# SCH_USB-Hub-Reader_2024-05-11.net
KiCad netlist of a schematic drawn in EasyEDA
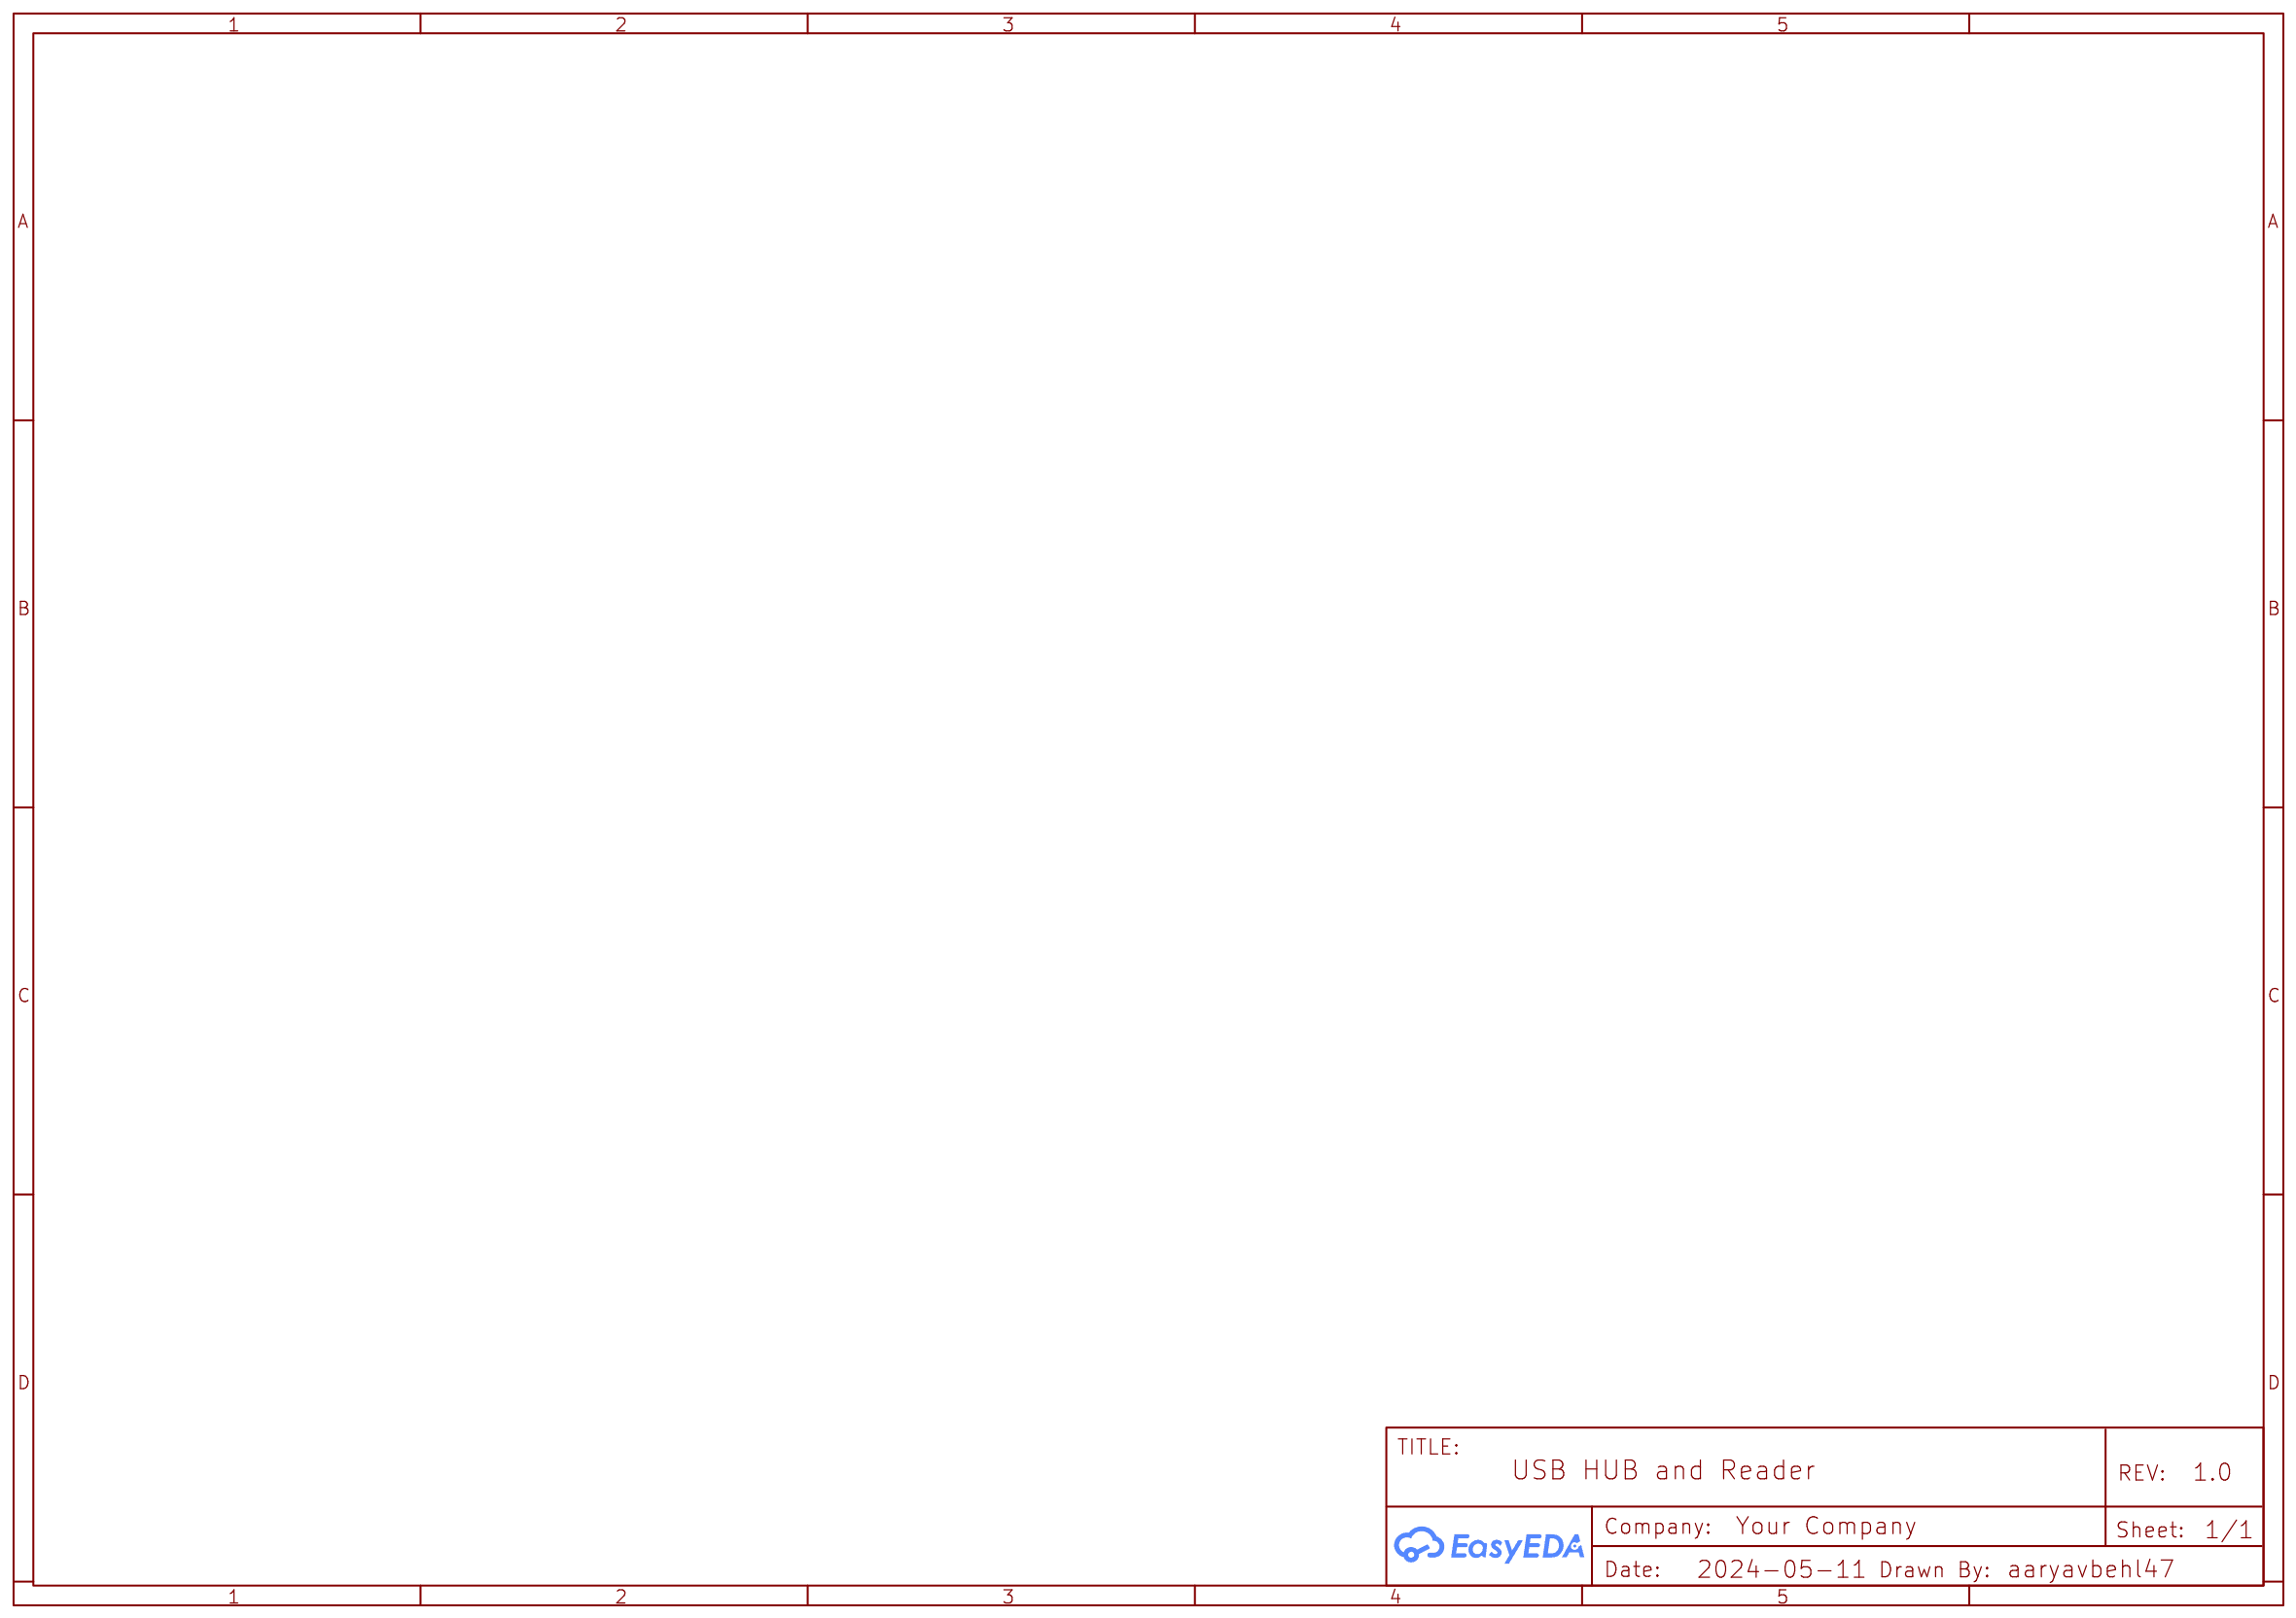
[diagram p0: Sheet_1]
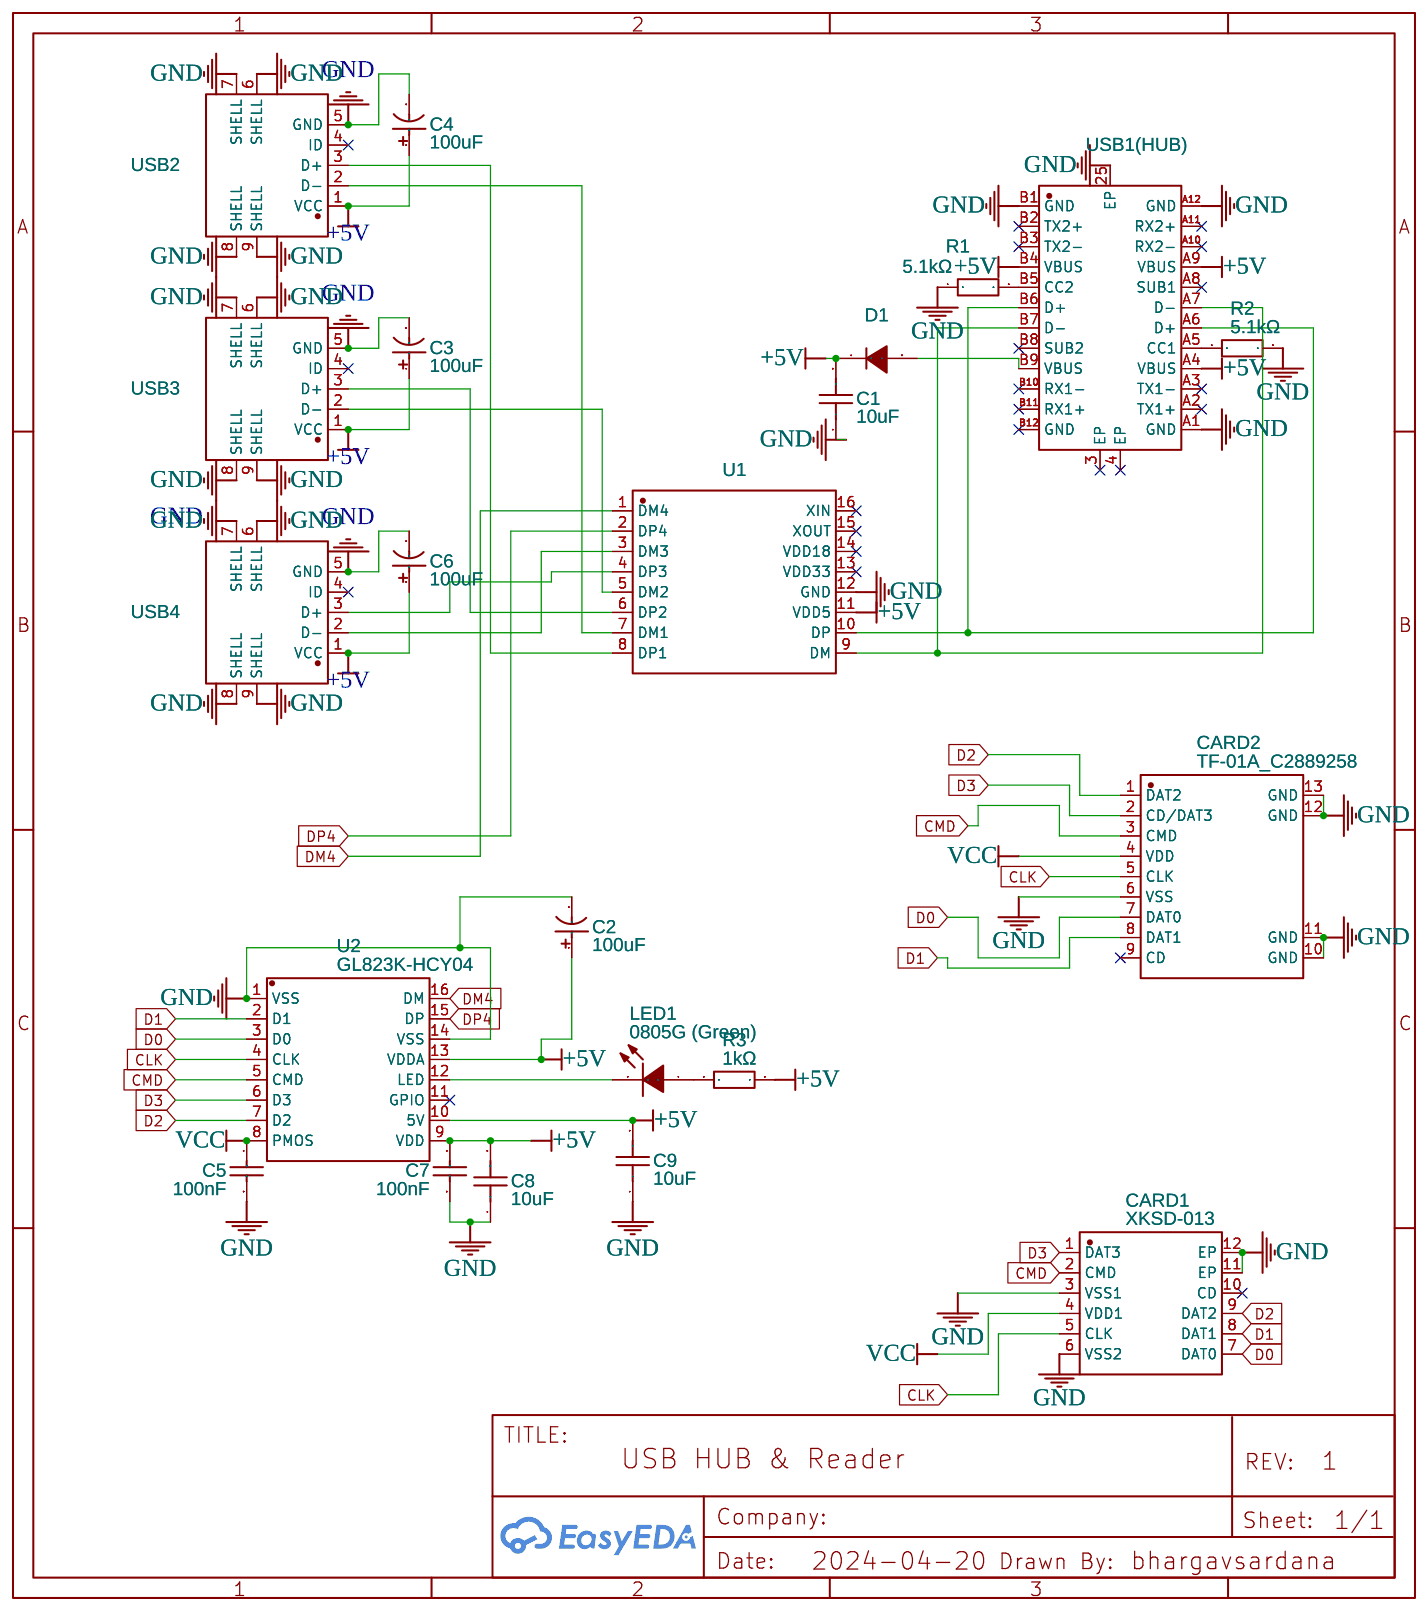
[diagram p1: hub schematics]

(export (version "E")
  (design (tool "Eeschema 10.0.6"))
  (components
    (comp (ref "C1")
      (value "10uF")
      (fields
        (field (name "Manufacturer Part") "CL10A106KP8NNNC")
        (field (name "Manufacturer") "SAMSUNG(三星)")
      )
      (libsource (lib "") (part "CL10A106KP8NNNC"))
    )
    (comp (ref "C2")
      (value "100uF")
      (fields (field (name "Manufacturer Part") "RVT1J101M1010") (field (name "Manufacturer") "ROQANG(容强)"))
      (libsource (lib "") (part "RVT1J101M1010-C72481"))
    )
    (comp (ref "C3")
      (value "100uF")
      (fields (field (name "Manufacturer Part") "RVT1J101M1010") (field (name "Manufacturer") "ROQANG(容强)"))
      (libsource (lib "") (part "RVT1J101M1010-C72481"))
    )
    (comp (ref "C4")
      (value "100uF")
      (fields (field (name "Manufacturer Part") "RVT1J101M1010") (field (name "Manufacturer") "ROQANG(容强)"))
      (libsource (lib "") (part "RVT1J101M1010-C72481"))
    )
    (comp (ref "C5")
      (value "100nF")
      (fields
        (field (name "Manufacturer Part") "CL05B104KO5NNNC")
        (field (name "Manufacturer") "SAMSUNG(三星)")
      )
      (libsource (lib "") (part "CL05B104KO5NNNC"))
    )
    (comp (ref "C6")
      (value "100uF")
      (fields (field (name "Manufacturer Part") "RVT1J101M1010") (field (name "Manufacturer") "ROQANG(容强)"))
      (libsource (lib "") (part "RVT1J101M1010-C72481"))
    )
    (comp (ref "C7")
      (value "100nF")
      (fields
        (field (name "Manufacturer Part") "CL05B104KO5NNNC")
        (field (name "Manufacturer") "SAMSUNG(三星)")
      )
      (libsource (lib "") (part "CL05B104KO5NNNC"))
    )
    (comp (ref "C8")
      (value "10uF")
      (fields
        (field (name "Manufacturer Part") "CL10A106KP8NNNC")
        (field (name "Manufacturer") "SAMSUNG(三星)")
      )
      (libsource (lib "") (part "CL10A106KP8NNNC"))
    )
    (comp (ref "C9")
      (value "10uF")
      (fields
        (field (name "Manufacturer Part") "CL10A106KP8NNNC")
        (field (name "Manufacturer") "SAMSUNG(三星)")
      )
      (libsource (lib "") (part "CL10A106KP8NNNC"))
    )
    (comp (ref "CARD1")
      (value "XKSD-013")
      (fields (field (name "Manufacturer") "XKB Connectivity(中国星坤)"))
      (libsource (lib "") (part "XKSD-013"))
    )
    (comp (ref "CARD2")
      (value "TF-01A_C2889258")
      (fields (field (name "Manufacturer Part") "TF-01A") (field (name "Manufacturer") "Yuandi(台湾元迪)"))
      (libsource (lib "") (part "TF-01A_C2889258"))
    )
    (comp (ref "D1")
      (value "NSR0320MW2T1G")
      (fields (field (name "Manufacturer") "onsemi(安森美)"))
      (libsource (lib "") (part "NSR0320MW2T1G"))
    )
    (comp (ref "LED1")
      (value "0805G (Green)")
      (fields (field (name "Manufacturer Part") "KT-0805G") (field (name "Manufacturer") "KENTO"))
      (libsource (lib "") (part "0805G (Green)"))
    )
    (comp (ref "R1")
      (value "5.1kΩ")
      (fields
        (field (name "Manufacturer Part") "0402WGF5101TCE")
        (field (name "Manufacturer") "UNI-ROYAL(厚声)")
      )
      (libsource (lib "") (part "0402WGF5101TCE"))
    )
    (comp (ref "R2")
      (value "5.1kΩ")
      (fields
        (field (name "Manufacturer Part") "0402WGF5101TCE")
        (field (name "Manufacturer") "UNI-ROYAL(厚声)")
      )
      (libsource (lib "") (part "0402WGF5101TCE"))
    )
    (comp (ref "R3")
      (value "1kΩ")
      (fields
        (field (name "Manufacturer Part") "0402WGF1001TCE")
        (field (name "Manufacturer") "UNI-ROYAL(厚声)")
      )
      (libsource (lib "") (part "0402WGF1001TCE"))
    )
    (comp (ref "U1")
      (value "SL2.1A")
      (fields (field (name "Manufacturer") "CoreChips(和芯润德)"))
      (libsource (lib "") (part "SL2.1A"))
    )
    (comp (ref "U2")
      (value "GL823K-HCY04")
      (fields (field (name "Manufacturer") "GENESYS(创惟)"))
      (libsource (lib "") (part "GL823K-HCY04"))
    )
    (comp (ref "USB1(HUB)")
      (value "TYPE-C 24P QT")
      (fields (field (name "Manufacturer") "SHOU HAN(首韩)"))
      (libsource (lib "") (part "TYPE-C 24P QT"))
    )
    (comp (ref "USB2")
      (value "U224-051N-3GRA035")
      (fields (field (name "Manufacturer") "XKB Connectivity(中国星坤)"))
      (libsource (lib "") (part "U224-051N-3GRA035"))
    )
    (comp (ref "USB3")
      (value "U224-051N-3GRA035")
      (fields (field (name "Manufacturer") "XKB Connectivity(中国星坤)"))
      (libsource (lib "") (part "U224-051N-3GRA035"))
    )
    (comp (ref "USB4")
      (value "U224-051N-3GRA035")
      (fields (field (name "Manufacturer") "XKB Connectivity(中国星坤)"))
      (libsource (lib "") (part "U224-051N-3GRA035"))
    )
  )
  (nets
    (net (code "1") (name "+5V") (class "Default")
      (node (ref "C1") (pin "2") (pinfunction "2_2") (pintype "unspecified"))
      (node (ref "C2") (pin "1") (pinfunction "1_1") (pintype "input"))
      (node (ref "C3") (pin "1") (pinfunction "1_1") (pintype "input"))
      (node (ref "C4") (pin "1") (pinfunction "1_1") (pintype "input"))
      (node (ref "C6") (pin "1") (pinfunction "1_1") (pintype "input"))
      (node (ref "C7") (pin "1") (pinfunction "1_1") (pintype "input"))
      (node (ref "C8") (pin "2") (pinfunction "2_2") (pintype "unspecified"))
      (node (ref "C9") (pin "2") (pinfunction "2_2") (pintype "unspecified"))
      (node (ref "D1") (pin "1") (pinfunction "C_1") (pintype "unspecified"))
      (node (ref "R3") (pin "2") (pinfunction "2_2") (pintype "input"))
      (node (ref "U1") (pin "11") (pinfunction "VDD5_11") (pintype "unspecified"))
      (node (ref "U2") (pin "10") (pinfunction "5V_10") (pintype "unspecified"))
      (node (ref "U2") (pin "13") (pinfunction "VDDA_13") (pintype "unspecified"))
      (node (ref "U2") (pin "9") (pinfunction "VDD_9") (pintype "unspecified"))
      (node (ref "USB1(HUB)") (pin "A4") (pinfunction "VBUS_A4") (pintype "unspecified"))
      (node (ref "USB1(HUB)") (pin "A9") (pinfunction "VBUS_A9") (pintype "unspecified"))
      (node (ref "USB1(HUB)") (pin "B4") (pinfunction "VBUS_B4") (pintype "unspecified"))
      (node (ref "USB2") (pin "1") (pinfunction "VCC_1") (pintype "unspecified"))
      (node (ref "USB3") (pin "1") (pinfunction "VCC_1") (pintype "unspecified"))
      (node (ref "USB4") (pin "1") (pinfunction "VCC_1") (pintype "unspecified"))
    )
    (net (code "2") (name "CLK") (class "Default")
      (node (ref "CARD1") (pin "5") (pinfunction "CLK_5") (pintype "unspecified"))
      (node (ref "CARD2") (pin "5") (pinfunction "CLK_5") (pintype "unspecified"))
      (node (ref "U2") (pin "4") (pinfunction "CLK_4") (pintype "unspecified"))
    )
    (net (code "3") (name "CMD") (class "Default")
      (node (ref "CARD1") (pin "2") (pinfunction "CMD_2") (pintype "unspecified"))
      (node (ref "CARD2") (pin "3") (pinfunction "CMD_3") (pintype "unspecified"))
      (node (ref "U2") (pin "5") (pinfunction "CMD_5") (pintype "unspecified"))
    )
    (net (code "4") (name "D0") (class "Default")
      (node (ref "CARD1") (pin "7") (pinfunction "DAT0_7") (pintype "unspecified"))
      (node (ref "CARD2") (pin "7") (pinfunction "DAT0_7") (pintype "unspecified"))
      (node (ref "U2") (pin "3") (pinfunction "D0_3") (pintype "unspecified"))
    )
    (net (code "5") (name "D1") (class "Default")
      (node (ref "CARD1") (pin "8") (pinfunction "DAT1_8") (pintype "unspecified"))
      (node (ref "CARD2") (pin "8") (pinfunction "DAT1_8") (pintype "unspecified"))
      (node (ref "U2") (pin "2") (pinfunction "D1_2") (pintype "unspecified"))
    )
    (net (code "6") (name "D2") (class "Default")
      (node (ref "CARD1") (pin "9") (pinfunction "DAT2_9") (pintype "unspecified"))
      (node (ref "CARD2") (pin "1") (pinfunction "DAT2_1") (pintype "unspecified"))
      (node (ref "U2") (pin "7") (pinfunction "D2_7") (pintype "unspecified"))
    )
    (net (code "7") (name "D3") (class "Default")
      (node (ref "CARD1") (pin "1") (pinfunction "DAT3_1") (pintype "unspecified"))
      (node (ref "CARD2") (pin "2") (pinfunction "CD/DAT3_2") (pintype "unspecified"))
      (node (ref "U2") (pin "6") (pinfunction "D3_6") (pintype "unspecified"))
    )
    (net (code "8") (name "DM4") (class "Default")
      (node (ref "U1") (pin "1") (pinfunction "DM4_1") (pintype "unspecified"))
      (node (ref "U2") (pin "16") (pinfunction "DM_16") (pintype "unspecified"))
    )
    (net (code "9") (name "DP4") (class "Default")
      (node (ref "U1") (pin "2") (pinfunction "DP4_2") (pintype "unspecified"))
      (node (ref "U2") (pin "15") (pinfunction "DP_15") (pintype "unspecified"))
    )
    (net (code "10") (name "GND") (class "Default")
      (node (ref "C1") (pin "1") (pinfunction "1_1") (pintype "unspecified"))
      (node (ref "C2") (pin "2") (pinfunction "2_2") (pintype "input"))
      (node (ref "C3") (pin "2") (pinfunction "2_2") (pintype "input"))
      (node (ref "C4") (pin "2") (pinfunction "2_2") (pintype "input"))
      (node (ref "C5") (pin "2") (pinfunction "2_2") (pintype "input"))
      (node (ref "C6") (pin "2") (pinfunction "2_2") (pintype "input"))
      (node (ref "C7") (pin "2") (pinfunction "2_2") (pintype "input"))
      (node (ref "C8") (pin "1") (pinfunction "1_1") (pintype "unspecified"))
      (node (ref "C9") (pin "1") (pinfunction "1_1") (pintype "unspecified"))
      (node (ref "CARD1") (pin "11") (pinfunction "EP_11") (pintype "unspecified"))
      (node (ref "CARD1") (pin "12") (pinfunction "EP_12") (pintype "unspecified"))
      (node (ref "CARD1") (pin "3") (pinfunction "VSS1_3") (pintype "unspecified"))
      (node (ref "CARD1") (pin "6") (pinfunction "VSS2_6") (pintype "unspecified"))
      (node (ref "CARD2") (pin "10") (pinfunction "GND_10") (pintype "unspecified"))
      (node (ref "CARD2") (pin "11") (pinfunction "GND_11") (pintype "unspecified"))
      (node (ref "CARD2") (pin "12") (pinfunction "GND_12") (pintype "unspecified"))
      (node (ref "CARD2") (pin "13") (pinfunction "GND_13") (pintype "unspecified"))
      (node (ref "CARD2") (pin "6") (pinfunction "VSS_6") (pintype "unspecified"))
      (node (ref "R1") (pin "1") (pinfunction "1_1") (pintype "input"))
      (node (ref "R2") (pin "2") (pinfunction "2_2") (pintype "input"))
      (node (ref "U1") (pin "12") (pinfunction "GND_12") (pintype "unspecified"))
      (node (ref "U2") (pin "1") (pinfunction "VSS_1") (pintype "unspecified"))
      (node (ref "U2") (pin "14") (pinfunction "VSS_14") (pintype "unspecified"))
      (node (ref "USB1(HUB)") (pin "25") (pinfunction "EP_25") (pintype "unspecified"))
      (node (ref "USB1(HUB)") (pin "A1") (pinfunction "GND_A1") (pintype "unspecified"))
      (node (ref "USB1(HUB)") (pin "A12") (pinfunction "GND_A12") (pintype "unspecified"))
      (node (ref "USB1(HUB)") (pin "B1") (pinfunction "GND_B1") (pintype "unspecified"))
      (node (ref "USB2") (pin "5") (pinfunction "GND_5") (pintype "unspecified"))
      (node (ref "USB2") (pin "6") (pinfunction "SHELL_6") (pintype "unspecified"))
      (node (ref "USB2") (pin "7") (pinfunction "SHELL_7") (pintype "unspecified"))
      (node (ref "USB2") (pin "8") (pinfunction "SHELL_8") (pintype "unspecified"))
      (node (ref "USB2") (pin "9") (pinfunction "SHELL_9") (pintype "unspecified"))
      (node (ref "USB3") (pin "5") (pinfunction "GND_5") (pintype "unspecified"))
      (node (ref "USB3") (pin "6") (pinfunction "SHELL_6") (pintype "unspecified"))
      (node (ref "USB3") (pin "7") (pinfunction "SHELL_7") (pintype "unspecified"))
      (node (ref "USB3") (pin "8") (pinfunction "SHELL_8") (pintype "unspecified"))
      (node (ref "USB3") (pin "9") (pinfunction "SHELL_9") (pintype "unspecified"))
      (node (ref "USB4") (pin "5") (pinfunction "GND_5") (pintype "unspecified"))
      (node (ref "USB4") (pin "6") (pinfunction "SHELL_6") (pintype "unspecified"))
      (node (ref "USB4") (pin "7") (pinfunction "SHELL_7") (pintype "unspecified"))
      (node (ref "USB4") (pin "8") (pinfunction "SHELL_8") (pintype "unspecified"))
      (node (ref "USB4") (pin "9") (pinfunction "SHELL_9") (pintype "unspecified"))
    )
    (net (code "11") (name "Net-(D1-A)") (class "Default")
      (node (ref "D1") (pin "2") (pinfunction "A_2") (pintype "unspecified"))
      (node (ref "USB1(HUB)") (pin "B9") (pinfunction "VBUS_B9") (pintype "unspecified"))
    )
    (net (code "12") (name "Net-(LED1-A)") (class "Default")
      (node (ref "LED1") (pin "1") (pinfunction "A_1") (pintype "unspecified"))
      (node (ref "R3") (pin "1") (pinfunction "1_1") (pintype "input"))
    )
    (net (code "13") (name "Net-(LED1-K)") (class "Default")
      (node (ref "LED1") (pin "2") (pinfunction "K_2") (pintype "unspecified"))
      (node (ref "U2") (pin "12") (pinfunction "LED_12") (pintype "unspecified"))
    )
    (net (code "14") (name "Net-(U1-DM)") (class "Default")
      (node (ref "U1") (pin "9") (pinfunction "DM_9") (pintype "unspecified"))
      (node (ref "USB1(HUB)") (pin "A7") (pinfunction "D-_A7") (pintype "unspecified"))
      (node (ref "USB1(HUB)") (pin "B7") (pinfunction "D-_B7") (pintype "unspecified"))
    )
    (net (code "15") (name "Net-(U1-DM1)") (class "Default")
      (node (ref "U1") (pin "7") (pinfunction "DM1_7") (pintype "unspecified"))
      (node (ref "USB2") (pin "2") (pinfunction "D-_2") (pintype "unspecified"))
    )
    (net (code "16") (name "Net-(U1-DM2)") (class "Default")
      (node (ref "U1") (pin "5") (pinfunction "DM2_5") (pintype "unspecified"))
      (node (ref "USB3") (pin "2") (pinfunction "D-_2") (pintype "unspecified"))
    )
    (net (code "17") (name "Net-(U1-DM3)") (class "Default")
      (node (ref "U1") (pin "3") (pinfunction "DM3_3") (pintype "unspecified"))
      (node (ref "USB4") (pin "2") (pinfunction "D-_2") (pintype "unspecified"))
    )
    (net (code "18") (name "Net-(U1-DP)") (class "Default")
      (node (ref "U1") (pin "10") (pinfunction "DP_10") (pintype "unspecified"))
      (node (ref "USB1(HUB)") (pin "A6") (pinfunction "D+_A6") (pintype "unspecified"))
      (node (ref "USB1(HUB)") (pin "B6") (pinfunction "D+_B6") (pintype "unspecified"))
    )
    (net (code "19") (name "Net-(U1-DP1)") (class "Default")
      (node (ref "U1") (pin "8") (pinfunction "DP1_8") (pintype "unspecified"))
      (node (ref "USB2") (pin "3") (pinfunction "D+_3") (pintype "unspecified"))
    )
    (net (code "20") (name "Net-(U1-DP2)") (class "Default")
      (node (ref "U1") (pin "6") (pinfunction "DP2_6") (pintype "unspecified"))
      (node (ref "USB3") (pin "3") (pinfunction "D+_3") (pintype "unspecified"))
    )
    (net (code "21") (name "Net-(U1-DP3)") (class "Default")
      (node (ref "U1") (pin "4") (pinfunction "DP3_4") (pintype "unspecified"))
      (node (ref "USB4") (pin "3") (pinfunction "D+_3") (pintype "unspecified"))
    )
    (net (code "22") (name "Net-(USB1(HUB)-CC1)") (class "Default")
      (node (ref "R2") (pin "1") (pinfunction "1_1") (pintype "input"))
      (node (ref "USB1(HUB)") (pin "A5") (pinfunction "CC1_A5") (pintype "unspecified"))
    )
    (net (code "23") (name "Net-(USB1(HUB)-CC2)") (class "Default")
      (node (ref "R1") (pin "2") (pinfunction "2_2") (pintype "input"))
      (node (ref "USB1(HUB)") (pin "B5") (pinfunction "CC2_B5") (pintype "unspecified"))
    )
    (net (code "24") (name "VCC") (class "Default")
      (node (ref "C5") (pin "1") (pinfunction "1_1") (pintype "input"))
      (node (ref "CARD1") (pin "4") (pinfunction "VDD1_4") (pintype "unspecified"))
      (node (ref "CARD2") (pin "4") (pinfunction "VDD_4") (pintype "unspecified"))
      (node (ref "U2") (pin "8") (pinfunction "PMOS_8") (pintype "unspecified"))
    )
    (net (code "25") (name "unconnected-(CARD1-CD-Pad10)") (class "Default")
      (node (ref "CARD1") (pin "10") (pinfunction "CD_10") (pintype "unspecified+no_connect"))
    )
    (net (code "26") (name "unconnected-(CARD2-CD-Pad9)") (class "Default")
      (node (ref "CARD2") (pin "9") (pinfunction "CD_9") (pintype "unspecified+no_connect"))
    )
    (net (code "27") (name "unconnected-(U1-VDD18-Pad14)") (class "Default")
      (node (ref "U1") (pin "14") (pinfunction "VDD18_14") (pintype "unspecified+no_connect"))
    )
    (net (code "28") (name "unconnected-(U1-VDD33-Pad13)") (class "Default")
      (node (ref "U1") (pin "13") (pinfunction "VDD33_13") (pintype "unspecified+no_connect"))
    )
    (net (code "29") (name "unconnected-(U1-XIN-Pad16)") (class "Default")
      (node (ref "U1") (pin "16") (pinfunction "XIN_16") (pintype "unspecified+no_connect"))
    )
    (net (code "30") (name "unconnected-(U1-XOUT-Pad15)") (class "Default")
      (node (ref "U1") (pin "15") (pinfunction "XOUT_15") (pintype "unspecified+no_connect"))
    )
    (net (code "31") (name "unconnected-(U2-GPIO-Pad11)") (class "Default")
      (node (ref "U2") (pin "11") (pinfunction "GPIO_11") (pintype "unspecified+no_connect"))
    )
    (net (code "32") (name "unconnected-(USB1(HUB)-EP-Pad3)") (class "Default")
      (node (ref "USB1(HUB)") (pin "3") (pinfunction "EP_3") (pintype "unspecified+no_connect"))
    )
    (net (code "33") (name "unconnected-(USB1(HUB)-EP-Pad4)") (class "Default")
      (node (ref "USB1(HUB)") (pin "4") (pinfunction "EP_4") (pintype "unspecified+no_connect"))
    )
    (net (code "34") (name "unconnected-(USB1(HUB)-GND-PadB12)") (class "Default")
      (node (ref "USB1(HUB)") (pin "B12") (pinfunction "GND_B12") (pintype "unspecified+no_connect"))
    )
    (net (code "35") (name "unconnected-(USB1(HUB)-RX1+-PadB11)") (class "Default")
      (node (ref "USB1(HUB)") (pin "B11") (pinfunction "RX1+_B11") (pintype "unspecified+no_connect"))
    )
    (net (code "36") (name "unconnected-(USB1(HUB)-RX1--PadB10)") (class "Default")
      (node (ref "USB1(HUB)") (pin "B10") (pinfunction "RX1-_B10") (pintype "unspecified+no_connect"))
    )
    (net (code "37") (name "unconnected-(USB1(HUB)-RX2+-PadA11)") (class "Default")
      (node (ref "USB1(HUB)") (pin "A11") (pinfunction "RX2+_A11") (pintype "unspecified+no_connect"))
    )
    (net (code "38") (name "unconnected-(USB1(HUB)-RX2--PadA10)") (class "Default")
      (node (ref "USB1(HUB)") (pin "A10") (pinfunction "RX2-_A10") (pintype "unspecified+no_connect"))
    )
    (net (code "39") (name "unconnected-(USB1(HUB)-SUB1-PadA8)") (class "Default")
      (node (ref "USB1(HUB)") (pin "A8") (pinfunction "SUB1_A8") (pintype "unspecified+no_connect"))
    )
    (net (code "40") (name "unconnected-(USB1(HUB)-SUB2-PadB8)") (class "Default")
      (node (ref "USB1(HUB)") (pin "B8") (pinfunction "SUB2_B8") (pintype "unspecified+no_connect"))
    )
    (net (code "41") (name "unconnected-(USB1(HUB)-TX1+-PadA2)") (class "Default")
      (node (ref "USB1(HUB)") (pin "A2") (pinfunction "TX1+_A2") (pintype "unspecified+no_connect"))
    )
    (net (code "42") (name "unconnected-(USB1(HUB)-TX1--PadA3)") (class "Default")
      (node (ref "USB1(HUB)") (pin "A3") (pinfunction "TX1-_A3") (pintype "unspecified+no_connect"))
    )
    (net (code "43") (name "unconnected-(USB1(HUB)-TX2+-PadB2)") (class "Default")
      (node (ref "USB1(HUB)") (pin "B2") (pinfunction "TX2+_B2") (pintype "unspecified+no_connect"))
    )
    (net (code "44") (name "unconnected-(USB1(HUB)-TX2--PadB3)") (class "Default")
      (node (ref "USB1(HUB)") (pin "B3") (pinfunction "TX2-_B3") (pintype "unspecified+no_connect"))
    )
    (net (code "45") (name "unconnected-(USB2-ID-Pad4)") (class "Default")
      (node (ref "USB2") (pin "4") (pinfunction "ID_4") (pintype "unspecified+no_connect"))
    )
    (net (code "46") (name "unconnected-(USB3-ID-Pad4)") (class "Default")
      (node (ref "USB3") (pin "4") (pinfunction "ID_4") (pintype "unspecified+no_connect"))
    )
    (net (code "47") (name "unconnected-(USB4-ID-Pad4)") (class "Default")
      (node (ref "USB4") (pin "4") (pinfunction "ID_4") (pintype "unspecified+no_connect"))
    )
  )
)
